# CONNECTION.net
KiCad netlist of a schematic drawn in Altium Designer
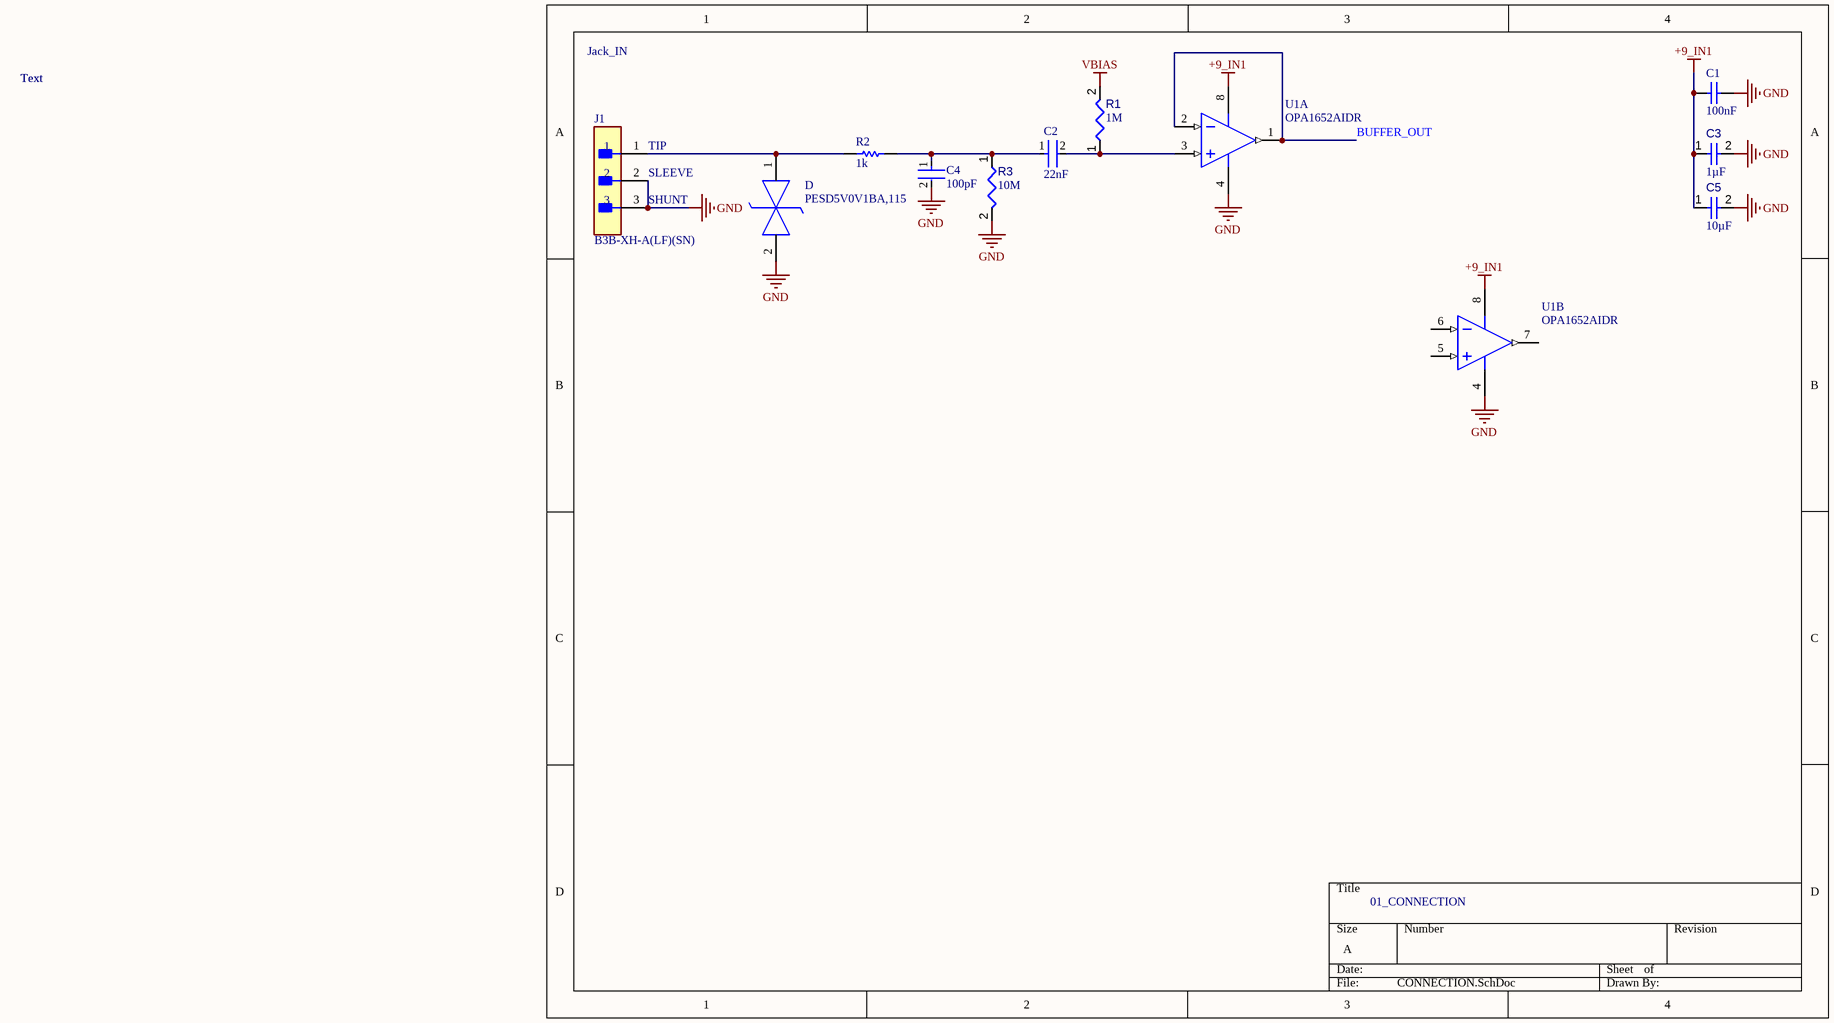
[diagram p0: CONNECTION.SchDoc]

(export (version "E")
  (design (tool "Eeschema 10.0.6"))
  (components
    (comp (ref "C1")
      (value "100nF")
      (footprint "KEMT-1206-2_N")
      (description "Multilayer Ceramic Capacitors MLCC - SMD/SMT 50V 0.1uF X7R 1206 10%")
      (fields (field (name "TOLERANCE") "10%") (field (name "Comment") "C1206C104K5RACTU"))
      (libsource (lib "") (part "CAP-NP-2_1"))
    )
    (comp (ref "C2")
      (value "22nF")
      (footprint "FP-C1206C-EB-MFG")
      (description "1206 (3216METRIC) Ceramic Capacitor SMD Comm C0G 50V 0.022MUF ±5% C0G NP0")
      (fields (field (name "TOLERANCE") "5%") (field (name "Comment") "C1206C223J5GACTU"))
      (libsource (lib "Maksym Pleshyvtsev") (part "b4654b650e69147ec39a6b967a45e02"))
    )
    (comp (ref "C3")
      (value "1µF")
      (footprint "CAPC3216X180X20ML20")
      (description "Chip Capacitor, 1 uF, +/- 10%, 25 V, 1206 (3216 Metric)")
      (fields (field (name "TOLERANCE") "10%") (field (name "Comment") "Capacitor 1 uF +/- 10% 25 V 1206"))
      (libsource (lib "Maksym Pleshyvtsev") (part "CAP-NP-2"))
    )
    (comp (ref "C4")
      (value "100pF")
      (footprint "FP-C1206C-EB-MFG")
      (description "Multilayer Ceramic Capacitor, 100 pF, 50 V, ± 5%, C0G (NP0), 1206 [3216 Metric]")
      (fields (field (name "TOLERANCE") "5%") (field (name "Comment") "C1206C101J5GACTU"))
      (libsource (lib "Maksym Pleshyvtsev") (part "b4654b650e69147ec39a6b967a45e02"))
    )
    (comp (ref "C5")
      (value "10µF")
      (footprint "CAPC3216X180X50NL20T25")
      (description "Chip Capacitor, 10 uF, +/- 10%, 16 V, 1206 (3216 Metric)")
      (fields (field (name "TOLERANCE") "10%") (field (name "Comment") "Capacitor 10 uF +/- 10% 16 V 1206"))
      (libsource (lib "Maksym Pleshyvtsev") (part "CAP-NP-2"))
    )
    (comp (ref "D")
      (value "PESD5V0V1BA,115")
      (footprint "PESD5V0V1BA,115-Footprint-1")
      (description "ESD protection diodes / TVS diodes; NEXPERIA; PESD5V0V1BA, 115; 12.5 V; 4.8 A; 5 V; 5.8 V")
      (libsource (lib "Maksym Pleshyvtsev") (part "PESD5V0V1BA,115-Symbol-1"))
    )
    (comp (ref "J1")
      (value "B3B-XH-A(LF)(SN)")
      (footprint "FP-B3B-XH-A_LF_SN-MFG")
      (description "Connector Header, XH Series, 3 Position, 2.50mm, Through Hole, Press-Fit, Solder, Natural")
      (libsource (lib "Maksym Pleshyvtsev") (part "0d3f023dd272f625e17a2be33dea85f"))
    )
    (comp (ref "R1")
      (value "1M")
      (footprint "RC1206FR-071ML-Footprint-1")
      (description "Res Thick Film 1206 1M Ohm 1% 0.25W(1/4W) ±100ppm/C Pad SMD T/R")
      (fields (field (name "TOLERANCE") "1%") (field (name "Comment") "RC1206FR-071ML"))
      (libsource (lib "") (part "RES-2_1"))
    )
    (comp (ref "R2")
      (value "1k")
      (footprint "RESC3116X70X50ML13T20")
      (description "Chip Resistor, 1 KOhm, +/- 1%, 0.25 W, -55 to 155 degC, 1206 (3216 Metric)")
      (fields (field (name "TOLERANCE") "1%") (field (name "POWER") "250mW"))
      (libsource (lib "Maksym Pleshyvtsev") (part "RES-2"))
    )
    (comp (ref "R3")
      (value "10M")
      (footprint "RC1206FR-0710ML-Footprint-1")
      (description "250mW Thick Film Resistors 200V ±100ppm/℃ ±1% 10MΩ 1206 Chip Resistor - Surface Mount ROHS")
      (fields (field (name "TOLERANCE") "1%") (field (name "Comment") "RC1206FR-0710ML"))
      (libsource (lib "") (part "RES-2_1"))
    )
    (comp (ref "U1")
      (value "OPA1652AIDR")
      (footprint "D0008A_N")
      (description "IC AUDIO 2 CIRCUIT 8SOIC Audio Amplifier 2 Circuit Rail-to-Rail 8-SOIC")
      (libsource (lib "Maksym Pleshyvtsev") (part "TI-OPA-8_2"))
    )
  )
  (nets
    (net (code "1") (name "+9_IN1") (class "Default")
      (node (ref "C1") (pin "2") (pinfunction "2_2") (pintype "passive"))
      (node (ref "C3") (pin "1") (pinfunction "1_1") (pintype "passive"))
      (node (ref "C5") (pin "1") (pinfunction "1_1") (pintype "passive"))
      (node (ref "U1") (pin "8") (pinfunction "V+_8") (pintype "power_in"))
    )
    (net (code "2") (name "/BUFFER_OUT") (class "Default")
      (node (ref "U1") (pin "1") (pinfunction "OUT_A_1") (pintype "output"))
      (node (ref "U1") (pin "2") (pinfunction "IN_A-_2") (pintype "input"))
    )
    (net (code "3") (name "GND") (class "Default")
      (node (ref "C1") (pin "1") (pinfunction "1_1") (pintype "passive"))
      (node (ref "C3") (pin "2") (pinfunction "2_2") (pintype "passive"))
      (node (ref "C4") (pin "2") (pinfunction "2_2") (pintype "passive"))
      (node (ref "C5") (pin "2") (pinfunction "2_2") (pintype "passive"))
      (node (ref "D") (pin "2") (pinfunction "K2_2") (pintype "passive"))
      (node (ref "J1") (pin "2") (pinfunction "2_2") (pintype "passive"))
      (node (ref "J1") (pin "3") (pinfunction "3_3") (pintype "passive"))
      (node (ref "R3") (pin "2") (pinfunction "2_2") (pintype "passive"))
      (node (ref "U1") (pin "4") (pinfunction "V-_4") (pintype "power_in"))
    )
    (net (code "4") (name "Net-(C2-Pad1)") (class "Default")
      (node (ref "C2") (pin "1") (pinfunction "1_1") (pintype "passive"))
      (node (ref "C4") (pin "1") (pinfunction "1_1") (pintype "passive"))
      (node (ref "R2") (pin "2") (pinfunction "2_2") (pintype "passive"))
      (node (ref "R3") (pin "1") (pinfunction "1_1") (pintype "passive"))
    )
    (net (code "5") (name "Net-(D-K1)") (class "Default")
      (node (ref "D") (pin "1") (pinfunction "K1_1") (pintype "passive"))
      (node (ref "J1") (pin "1") (pinfunction "1_1") (pintype "passive"))
      (node (ref "R2") (pin "1") (pinfunction "1_1") (pintype "passive"))
    )
    (net (code "6") (name "Net-(U1A-IN_A+)") (class "Default")
      (node (ref "C2") (pin "2") (pinfunction "2_2") (pintype "passive"))
      (node (ref "R1") (pin "1") (pinfunction "1_1") (pintype "passive"))
      (node (ref "U1") (pin "3") (pinfunction "IN_A+_3") (pintype "input"))
    )
    (net (code "7") (name "VBIAS") (class "Default")
      (node (ref "R1") (pin "2") (pinfunction "2_2") (pintype "passive"))
    )
    (net (code "8") (name "unconnected-(U1B-IN_B+-Pad5)") (class "Default")
      (node (ref "U1") (pin "5") (pinfunction "IN_B+_5") (pintype "input"))
    )
    (net (code "9") (name "unconnected-(U1B-IN_B--Pad6)") (class "Default")
      (node (ref "U1") (pin "6") (pinfunction "IN_B-_6") (pintype "input"))
    )
    (net (code "10") (name "unconnected-(U1B-OUT_B-Pad7)") (class "Default")
      (node (ref "U1") (pin "7") (pinfunction "OUT_B_7") (pintype "output"))
    )
  )
)
